# AnalogIO.net
KiCad netlist of a schematic drawn in Altium Designer
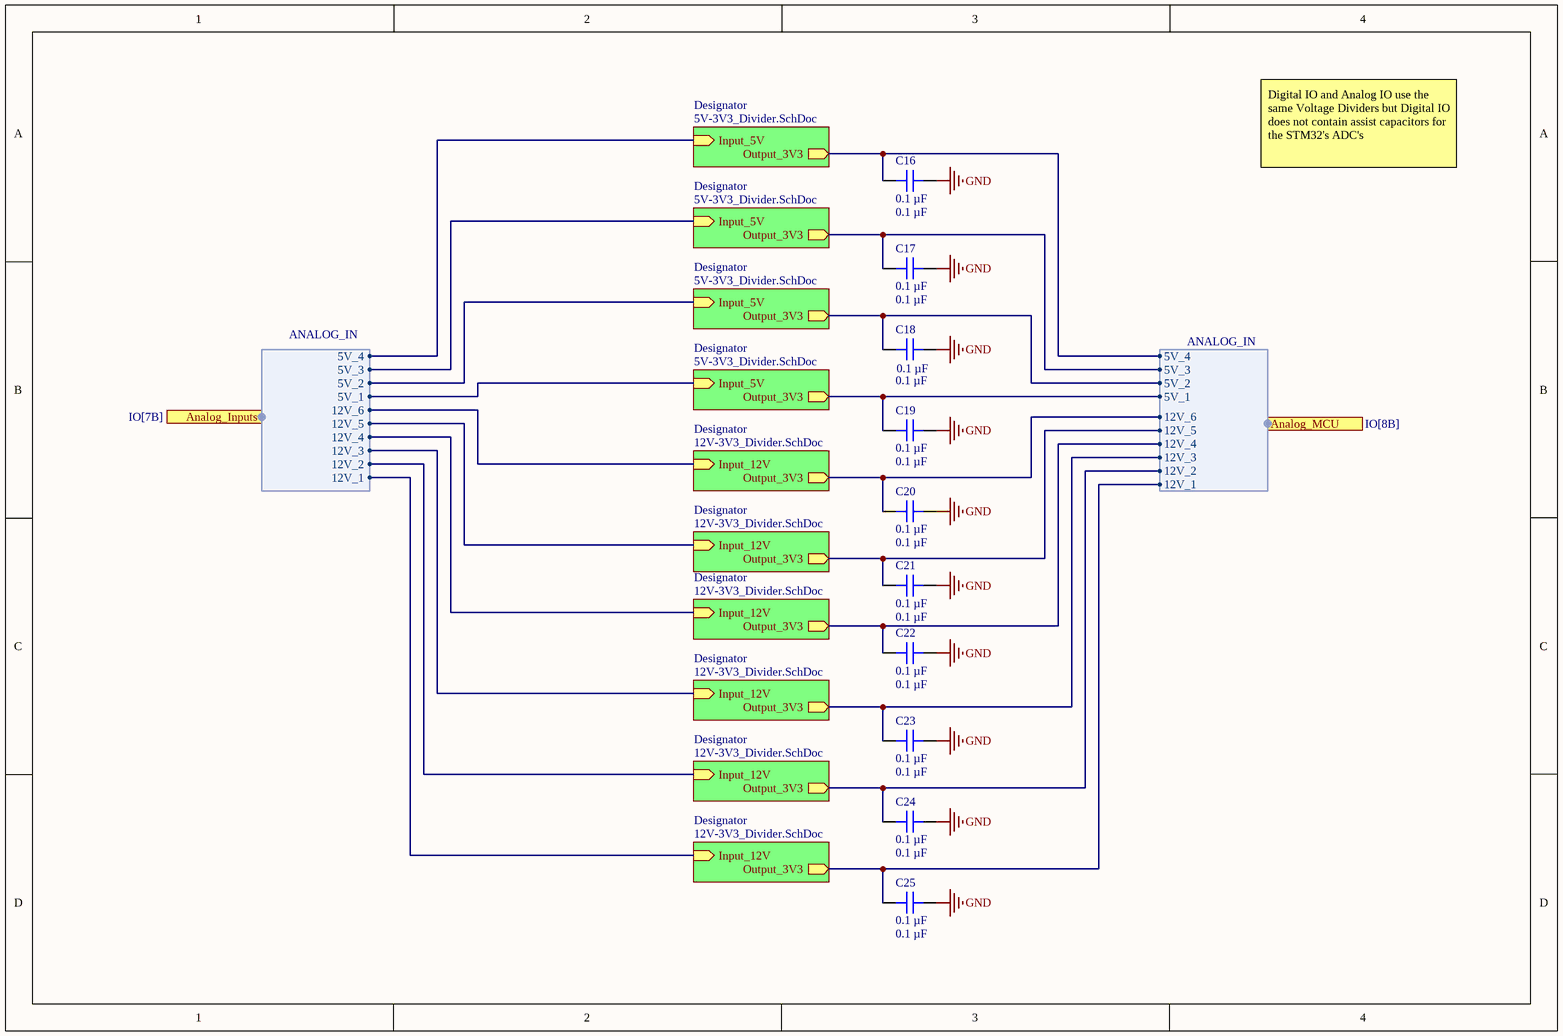
[diagram p0: AnalogIO.SchDoc]

(export (version "E")
  (design (tool "Eeschema 10.0.6"))
  (components
    (comp (ref "C16")
      (value "0.1 µF")
      (footprint "CAP 0603_1608")
      (description "CAP CER 0.1UF 16V X7R 0603")
      (fields (field (name "PART NUMBER") "CS0603KRX7R7BB104") (field (name "ALTIUM_VALUE") "0.1 µF"))
      (libsource (lib "altium_library") (part "Capacitor"))
    )
    (comp (ref "C17")
      (value "0.1 µF")
      (footprint "CAP 0603_1608")
      (description "CAP CER 0.1UF 16V X7R 0603")
      (fields (field (name "PART NUMBER") "CS0603KRX7R7BB104") (field (name "ALTIUM_VALUE") "0.1 µF"))
      (libsource (lib "altium_library") (part "Capacitor"))
    )
    (comp (ref "C18")
      (value "0.1 µF")
      (footprint "CAP 0603_1608")
      (description "CAP CER 0.1UF 16V X7R 0603")
      (fields (field (name "PART NUMBER") "CS0603KRX7R7BB104") (field (name "ALTIUM_VALUE") "0.1 µF"))
      (libsource (lib "altium_library") (part "Capacitor"))
    )
    (comp (ref "C19")
      (value "0.1 µF")
      (footprint "CAP 0603_1608")
      (description "CAP CER 0.1UF 16V X7R 0603")
      (fields (field (name "PART NUMBER") "CS0603KRX7R7BB104") (field (name "ALTIUM_VALUE") "0.1 µF"))
      (libsource (lib "altium_library") (part "Capacitor"))
    )
    (comp (ref "C20")
      (value "0.1 µF")
      (footprint "CAP 0603_1608")
      (description "CAP CER 0.1UF 16V X7R 0603")
      (fields (field (name "PART NUMBER") "CS0603KRX7R7BB104") (field (name "ALTIUM_VALUE") "0.1 µF"))
      (libsource (lib "altium_library") (part "Capacitor"))
    )
    (comp (ref "C21")
      (value "0.1 µF")
      (footprint "CAP 0603_1608")
      (description "CAP CER 0.1UF 16V X7R 0603")
      (fields (field (name "PART NUMBER") "CS0603KRX7R7BB104") (field (name "ALTIUM_VALUE") "0.1 µF"))
      (libsource (lib "altium_library") (part "Capacitor"))
    )
    (comp (ref "C22")
      (value "0.1 µF")
      (footprint "CAP 0603_1608")
      (description "CAP CER 0.1UF 16V X7R 0603")
      (fields (field (name "PART NUMBER") "CS0603KRX7R7BB104") (field (name "ALTIUM_VALUE") "0.1 µF"))
      (libsource (lib "altium_library") (part "Capacitor"))
    )
    (comp (ref "C23")
      (value "0.1 µF")
      (footprint "CAP 0603_1608")
      (description "CAP CER 0.1UF 16V X7R 0603")
      (fields (field (name "PART NUMBER") "CS0603KRX7R7BB104") (field (name "ALTIUM_VALUE") "0.1 µF"))
      (libsource (lib "altium_library") (part "Capacitor"))
    )
    (comp (ref "C24")
      (value "0.1 µF")
      (footprint "CAP 0603_1608")
      (description "CAP CER 0.1UF 16V X7R 0603")
      (fields (field (name "PART NUMBER") "CS0603KRX7R7BB104") (field (name "ALTIUM_VALUE") "0.1 µF"))
      (libsource (lib "altium_library") (part "Capacitor"))
    )
    (comp (ref "C25")
      (value "0.1 µF")
      (footprint "CAP 0603_1608")
      (description "CAP CER 0.1UF 16V X7R 0603")
      (fields (field (name "PART NUMBER") "CS0603KRX7R7BB104") (field (name "ALTIUM_VALUE") "0.1 µF"))
      (libsource (lib "altium_library") (part "Capacitor"))
    )
  )
  (nets
    (net (code "12") (name "/Output_3V3") (class "Default")
      (node (ref "C25") (pin "1") (pinfunction "1_1") (pintype "passive"))
    )
    (net (code "13") (name "/Output_3V3_1") (class "Default")
      (node (ref "C16") (pin "1") (pinfunction "1_1") (pintype "passive"))
    )
    (net (code "14") (name "/Output_3V3_2") (class "Default")
      (node (ref "C17") (pin "1") (pinfunction "1_1") (pintype "passive"))
    )
    (net (code "15") (name "/Output_3V3_3") (class "Default")
      (node (ref "C18") (pin "1") (pinfunction "1_1") (pintype "passive"))
    )
    (net (code "16") (name "/Output_3V3_4") (class "Default")
      (node (ref "C19") (pin "1") (pinfunction "1_1") (pintype "passive"))
    )
    (net (code "17") (name "/Output_3V3_5") (class "Default")
      (node (ref "C20") (pin "1") (pinfunction "1_1") (pintype "passive"))
    )
    (net (code "18") (name "/Output_3V3_6") (class "Default")
      (node (ref "C21") (pin "1") (pinfunction "1_1") (pintype "passive"))
    )
    (net (code "19") (name "/Output_3V3_7") (class "Default")
      (node (ref "C22") (pin "1") (pinfunction "1_1") (pintype "passive"))
    )
    (net (code "20") (name "/Output_3V3_8") (class "Default")
      (node (ref "C23") (pin "1") (pinfunction "1_1") (pintype "passive"))
    )
    (net (code "21") (name "/Output_3V3_9") (class "Default")
      (node (ref "C24") (pin "1") (pinfunction "1_1") (pintype "passive"))
    )
    (net (code "23") (name "GND") (class "Default")
      (node (ref "C16") (pin "2") (pinfunction "2_2") (pintype "passive"))
      (node (ref "C17") (pin "2") (pinfunction "2_2") (pintype "passive"))
      (node (ref "C18") (pin "2") (pinfunction "2_2") (pintype "passive"))
      (node (ref "C19") (pin "2") (pinfunction "2_2") (pintype "passive"))
      (node (ref "C20") (pin "2") (pinfunction "2_2") (pintype "passive"))
      (node (ref "C21") (pin "2") (pinfunction "2_2") (pintype "passive"))
      (node (ref "C22") (pin "2") (pinfunction "2_2") (pintype "passive"))
      (node (ref "C23") (pin "2") (pinfunction "2_2") (pintype "passive"))
      (node (ref "C24") (pin "2") (pinfunction "2_2") (pintype "passive"))
      (node (ref "C25") (pin "2") (pinfunction "2_2") (pintype "passive"))
    )
  )
)
